# USB.net
KiCad netlist of a schematic drawn in Altium Designer
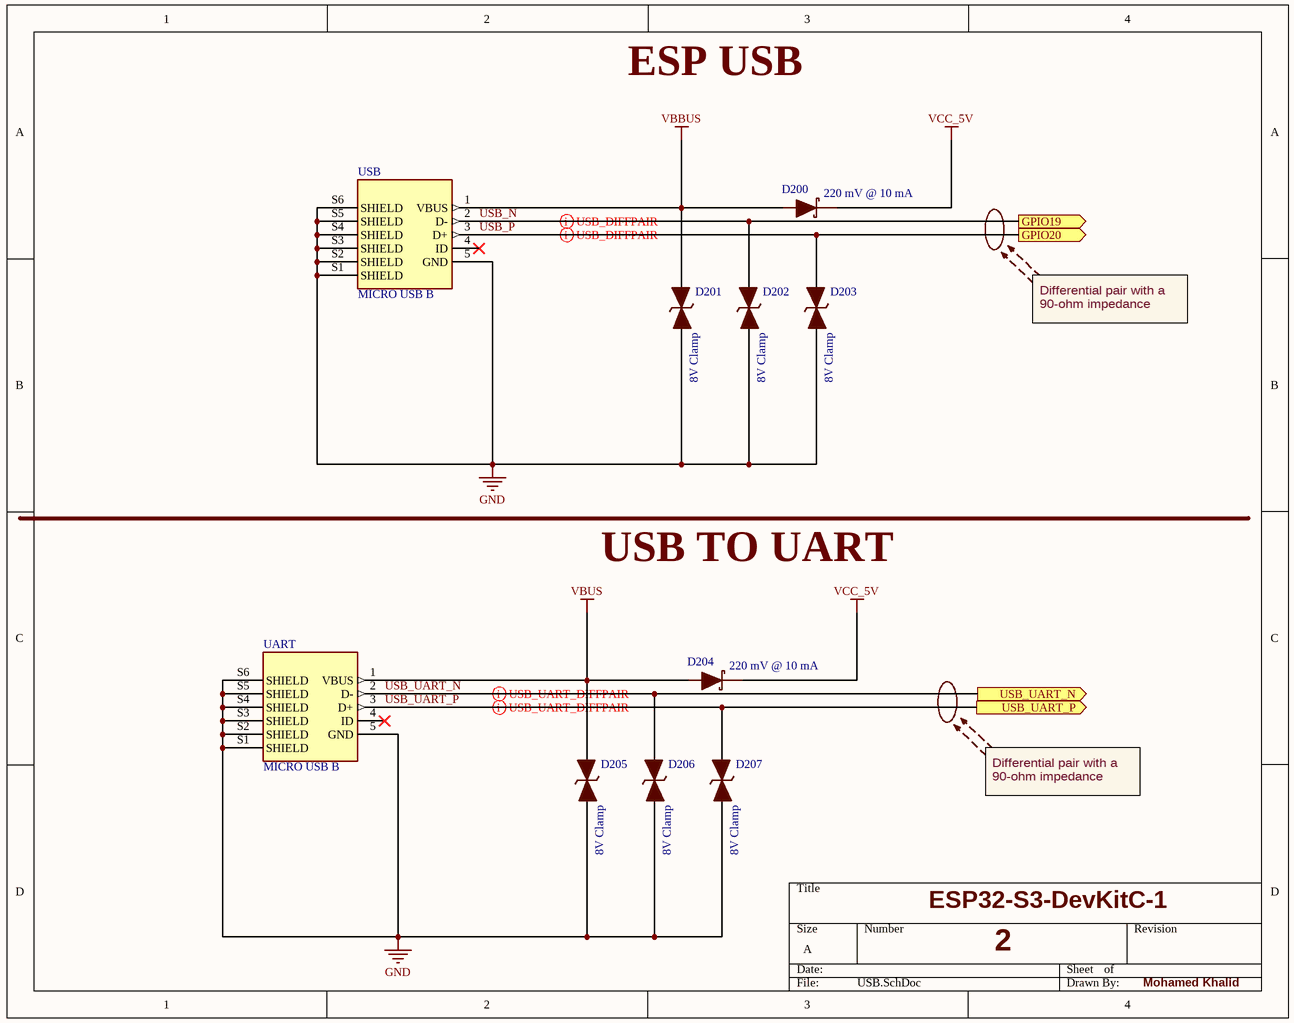
[diagram p0: USB.SchDoc]

(export (version "E")
  (design (tool "Eeschema 10.0.6"))
  (components
    (comp (ref "D200")
      (value "220 mV @ 10 mA")
      (footprint "SODFL1608X70N")
      (description "Diode 20 V 500mA Surface Mount SOD-882")
      (libsource (lib "ESP32_Integrated_Library") (part "CFSH05-20L TR PBFREE"))
    )
    (comp (ref "D201")
      (value "8V Clamp")
      (footprint "SODFL1006X40N")
      (description "8V (Typ) Clamp 7A (8/20µs) Ipp Tvs Diode Surface Mount 0201")
      (libsource (lib "ESP32_Integrated_Library") (part "ESDZV5-1BU2"))
    )
    (comp (ref "D202")
      (value "8V Clamp")
      (footprint "SODFL1006X40N")
      (description "8V (Typ) Clamp 7A (8/20µs) Ipp Tvs Diode Surface Mount 0201")
      (libsource (lib "ESP32_Integrated_Library") (part "ESDZV5-1BU2"))
    )
    (comp (ref "D203")
      (value "8V Clamp")
      (footprint "SODFL1006X40N")
      (description "8V (Typ) Clamp 7A (8/20µs) Ipp Tvs Diode Surface Mount 0201")
      (libsource (lib "ESP32_Integrated_Library") (part "ESDZV5-1BU2"))
    )
    (comp (ref "D204")
      (value "220 mV @ 10 mA")
      (footprint "SODFL1608X70N")
      (description "Diode 20 V 500mA Surface Mount SOD-882")
      (libsource (lib "ESP32_Integrated_Library") (part "CFSH05-20L TR PBFREE"))
    )
    (comp (ref "D205")
      (value "8V Clamp")
      (footprint "SODFL1006X40N")
      (description "8V (Typ) Clamp 7A (8/20µs) Ipp Tvs Diode Surface Mount 0201")
      (libsource (lib "ESP32_Integrated_Library") (part "ESDZV5-1BU2"))
    )
    (comp (ref "D206")
      (value "8V Clamp")
      (footprint "SODFL1006X40N")
      (description "8V (Typ) Clamp 7A (8/20µs) Ipp Tvs Diode Surface Mount 0201")
      (libsource (lib "ESP32_Integrated_Library") (part "ESDZV5-1BU2"))
    )
    (comp (ref "D207")
      (value "8V Clamp")
      (footprint "SODFL1006X40N")
      (description "8V (Typ) Clamp 7A (8/20µs) Ipp Tvs Diode Surface Mount 0201")
      (libsource (lib "ESP32_Integrated_Library") (part "ESDZV5-1BU2"))
    )
    (comp (ref "UART")
      (value "MICRO USB B")
      (footprint "AMPHENOL_10118193-0001LF")
      (fields (field (name "MF") "Amphenol ICC") (field (name "MP") "10118193-0001LF"))
      (libsource (lib "ESP32_Integrated_Library") (part "10118193-0001LF"))
    )
    (comp (ref "USB")
      (value "MICRO USB B")
      (footprint "AMPHENOL_10118193-0001LF")
      (fields (field (name "MF") "Amphenol ICC") (field (name "MP") "10118193-0001LF"))
      (libsource (lib "ESP32_Integrated_Library") (part "10118193-0001LF"))
    )
  )
  (nets
    (net (code "1") (name "/USB_N") (class "Default")
      (node (ref "D202") (pin "2") (pinfunction "2_2") (pintype "passive"))
      (node (ref "USB") (pin "2") (pinfunction "D-_2") (pintype "output"))
    )
    (net (code "2") (name "/USB_P") (class "Default")
      (node (ref "D203") (pin "2") (pinfunction "2_2") (pintype "passive"))
      (node (ref "USB") (pin "3") (pinfunction "D+_3") (pintype "output"))
    )
    (net (code "3") (name "/USB_UART_N") (class "Default")
      (node (ref "D206") (pin "2") (pinfunction "2_2") (pintype "passive"))
      (node (ref "UART") (pin "2") (pinfunction "D-_2") (pintype "output"))
    )
    (net (code "4") (name "/USB_UART_P") (class "Default")
      (node (ref "D207") (pin "2") (pinfunction "2_2") (pintype "passive"))
      (node (ref "UART") (pin "3") (pinfunction "D+_3") (pintype "output"))
    )
    (net (code "5") (name "GND") (class "Default")
      (node (ref "D201") (pin "1") (pinfunction "1_1") (pintype "passive"))
      (node (ref "D202") (pin "1") (pinfunction "1_1") (pintype "passive"))
      (node (ref "D203") (pin "1") (pinfunction "1_1") (pintype "passive"))
      (node (ref "D205") (pin "1") (pinfunction "1_1") (pintype "passive"))
      (node (ref "D206") (pin "1") (pinfunction "1_1") (pintype "passive"))
      (node (ref "D207") (pin "1") (pinfunction "1_1") (pintype "passive"))
      (node (ref "UART") (pin "5") (pinfunction "GND_5") (pintype "passive"))
      (node (ref "UART") (pin "S1") (pinfunction "SHIELD_S1") (pintype "passive"))
      (node (ref "UART") (pin "S2") (pinfunction "SHIELD_S2") (pintype "passive"))
      (node (ref "UART") (pin "S3") (pinfunction "SHIELD_S3") (pintype "passive"))
      (node (ref "UART") (pin "S4") (pinfunction "SHIELD_S4") (pintype "passive"))
      (node (ref "UART") (pin "S5") (pinfunction "SHIELD_S5") (pintype "passive"))
      (node (ref "UART") (pin "S6") (pinfunction "SHIELD_S6") (pintype "passive"))
      (node (ref "USB") (pin "5") (pinfunction "GND_5") (pintype "passive"))
      (node (ref "USB") (pin "S1") (pinfunction "SHIELD_S1") (pintype "passive"))
      (node (ref "USB") (pin "S2") (pinfunction "SHIELD_S2") (pintype "passive"))
      (node (ref "USB") (pin "S3") (pinfunction "SHIELD_S3") (pintype "passive"))
      (node (ref "USB") (pin "S4") (pinfunction "SHIELD_S4") (pintype "passive"))
      (node (ref "USB") (pin "S5") (pinfunction "SHIELD_S5") (pintype "passive"))
      (node (ref "USB") (pin "S6") (pinfunction "SHIELD_S6") (pintype "passive"))
    )
    (net (code "6") (name "VBBUS") (class "Default")
      (node (ref "D200") (pin "1") (pinfunction "K_1") (pintype "passive"))
      (node (ref "D201") (pin "2") (pinfunction "2_2") (pintype "passive"))
      (node (ref "USB") (pin "1") (pinfunction "VBUS_1") (pintype "output"))
    )
    (net (code "7") (name "VBUS") (class "Default")
      (node (ref "D204") (pin "1") (pinfunction "K_1") (pintype "passive"))
      (node (ref "D205") (pin "2") (pinfunction "2_2") (pintype "passive"))
      (node (ref "UART") (pin "1") (pinfunction "VBUS_1") (pintype "output"))
    )
    (net (code "8") (name "VCC_5V") (class "Default")
      (node (ref "D200") (pin "2") (pinfunction "A_2") (pintype "passive"))
      (node (ref "D204") (pin "2") (pinfunction "A_2") (pintype "passive"))
    )
    (net (code "9") (name "unconnected-(UART-ID-Pad4)") (class "Default")
      (node (ref "UART") (pin "4") (pinfunction "ID_4") (pintype "passive+no_connect"))
    )
    (net (code "10") (name "unconnected-(USB-ID-Pad4)") (class "Default")
      (node (ref "USB") (pin "4") (pinfunction "ID_4") (pintype "passive+no_connect"))
    )
  )
)
